# Encoder_velocistaEdu.net
KiCad netlist of a schematic drawn in EAGLE
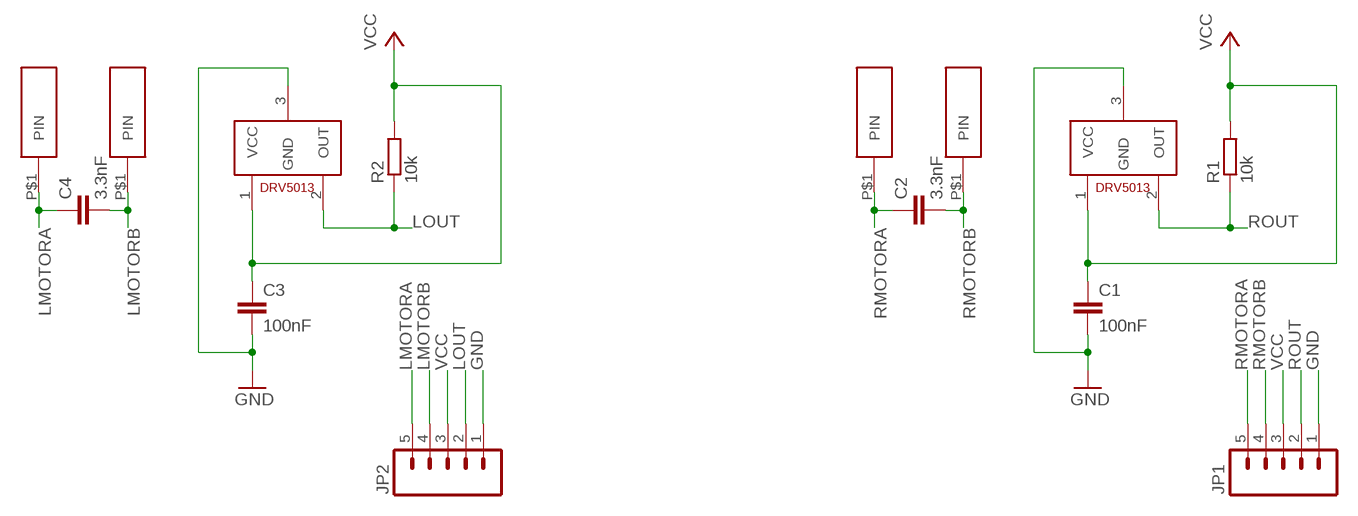
[diagram p0: schematic, sheet 1]

(export (version "E")
  (design (tool "Eeschema 10.0.6"))
  (components
    (comp (ref "C1")
      (value "100nF")
      (footprint "eagle-import:C0805")
      (libsource (lib "eagle-import") (part "C-EUC0805"))
    )
    (comp (ref "C2")
      (value "3.3nF")
      (footprint "eagle-import:C0805")
      (libsource (lib "eagle-import") (part "C-EUC0805"))
    )
    (comp (ref "C3")
      (value "100nF")
      (footprint "eagle-import:C0805")
      (libsource (lib "eagle-import") (part "C-EUC0805"))
    )
    (comp (ref "C4")
      (value "3.3nF")
      (footprint "eagle-import:C0805")
      (libsource (lib "eagle-import") (part "C-EUC0805"))
    )
    (comp (ref "JP1")
      (value "M05PTH")
      (footprint "eagle-import:1X05")
      (libsource (lib "eagle-import") (part "M05PTH"))
    )
    (comp (ref "JP2")
      (value "M05PTH")
      (footprint "eagle-import:1X05")
      (libsource (lib "eagle-import") (part "M05PTH"))
    )
    (comp (ref "R1")
      (value "10k")
      (footprint "eagle-import:M0805")
      (libsource (lib "eagle-import") (part "R-EU_M0805"))
    )
    (comp (ref "R2")
      (value "10k")
      (footprint "eagle-import:M0805")
      (libsource (lib "eagle-import") (part "R-EU_M0805"))
    )
    (comp (ref "U$1")
      (value "DRV5013")
      (footprint "eagle-import:DBZ_R-PDSO-G3")
      (libsource (lib "eagle-import") (part "DRV5013"))
    )
    (comp (ref "U$2")
      (value "TERMINAL_MOTOR_N20")
      (footprint "eagle-import:TERMINAL_MOTOR_N20")
      (libsource (lib "eagle-import") (part "TERMINAL_MOTOR_N20"))
    )
    (comp (ref "U$3")
      (value "TERMINAL_MOTOR_N20")
      (footprint "eagle-import:TERMINAL_MOTOR_N20")
      (libsource (lib "eagle-import") (part "TERMINAL_MOTOR_N20"))
    )
    (comp (ref "U$4")
      (value "TERMINAL_MOTOR_N20")
      (footprint "eagle-import:TERMINAL_MOTOR_N20")
      (libsource (lib "eagle-import") (part "TERMINAL_MOTOR_N20"))
    )
    (comp (ref "U$5")
      (value "TERMINAL_MOTOR_N20")
      (footprint "eagle-import:TERMINAL_MOTOR_N20")
      (libsource (lib "eagle-import") (part "TERMINAL_MOTOR_N20"))
    )
    (comp (ref "U$6")
      (value "DRV5013")
      (footprint "eagle-import:DBZ_R-PDSO-G3")
      (libsource (lib "eagle-import") (part "DRV5013"))
    )
  )
  (nets
    (net (code "1") (name "/LMOTORA") (class "Default")
      (node (ref "C4") (pin "1") (pinfunction "1_1") (pintype "passive"))
      (node (ref "JP2") (pin "5") (pinfunction "5_5") (pintype "passive"))
      (node (ref "U$4") (pin "P$1") (pinfunction "PIN_P$1") (pintype "bidirectional"))
    )
    (net (code "2") (name "/LMOTORB") (class "Default")
      (node (ref "C4") (pin "2") (pinfunction "2_2") (pintype "passive"))
      (node (ref "JP2") (pin "4") (pinfunction "4_4") (pintype "passive"))
      (node (ref "U$5") (pin "P$1") (pinfunction "PIN_P$1") (pintype "bidirectional"))
    )
    (net (code "3") (name "/LOUT") (class "Default")
      (node (ref "JP2") (pin "2") (pinfunction "2_2") (pintype "passive"))
      (node (ref "R2") (pin "1") (pinfunction "1_1") (pintype "passive"))
      (node (ref "U$6") (pin "2") (pinfunction "OUT_2") (pintype "bidirectional"))
    )
    (net (code "4") (name "/RMOTORA") (class "Default")
      (node (ref "C2") (pin "1") (pinfunction "1_1") (pintype "passive"))
      (node (ref "JP1") (pin "5") (pinfunction "5_5") (pintype "passive"))
      (node (ref "U$2") (pin "P$1") (pinfunction "PIN_P$1") (pintype "bidirectional"))
    )
    (net (code "5") (name "/RMOTORB") (class "Default")
      (node (ref "C2") (pin "2") (pinfunction "2_2") (pintype "passive"))
      (node (ref "JP1") (pin "4") (pinfunction "4_4") (pintype "passive"))
      (node (ref "U$3") (pin "P$1") (pinfunction "PIN_P$1") (pintype "bidirectional"))
    )
    (net (code "6") (name "/ROUT") (class "Default")
      (node (ref "JP1") (pin "2") (pinfunction "2_2") (pintype "passive"))
      (node (ref "R1") (pin "1") (pinfunction "1_1") (pintype "passive"))
      (node (ref "U$1") (pin "2") (pinfunction "OUT_2") (pintype "bidirectional"))
    )
    (net (code "7") (name "GND") (class "Default")
      (node (ref "C1") (pin "2") (pinfunction "2_2") (pintype "passive"))
      (node (ref "C3") (pin "2") (pinfunction "2_2") (pintype "passive"))
      (node (ref "JP1") (pin "1") (pinfunction "1_1") (pintype "passive"))
      (node (ref "JP2") (pin "1") (pinfunction "1_1") (pintype "passive"))
      (node (ref "U$1") (pin "3") (pinfunction "GND_3") (pintype "bidirectional"))
      (node (ref "U$6") (pin "3") (pinfunction "GND_3") (pintype "bidirectional"))
    )
    (net (code "8") (name "VCC") (class "Default")
      (node (ref "C1") (pin "1") (pinfunction "1_1") (pintype "passive"))
      (node (ref "C3") (pin "1") (pinfunction "1_1") (pintype "passive"))
      (node (ref "JP1") (pin "3") (pinfunction "3_3") (pintype "passive"))
      (node (ref "JP2") (pin "3") (pinfunction "3_3") (pintype "passive"))
      (node (ref "R1") (pin "2") (pinfunction "2_2") (pintype "passive"))
      (node (ref "R2") (pin "2") (pinfunction "2_2") (pintype "passive"))
      (node (ref "U$1") (pin "1") (pinfunction "VCC_1") (pintype "bidirectional"))
      (node (ref "U$6") (pin "1") (pinfunction "VCC_1") (pintype "bidirectional"))
    )
  )
)
